# al.net
KiCad netlist of a schematic drawn in EAGLE
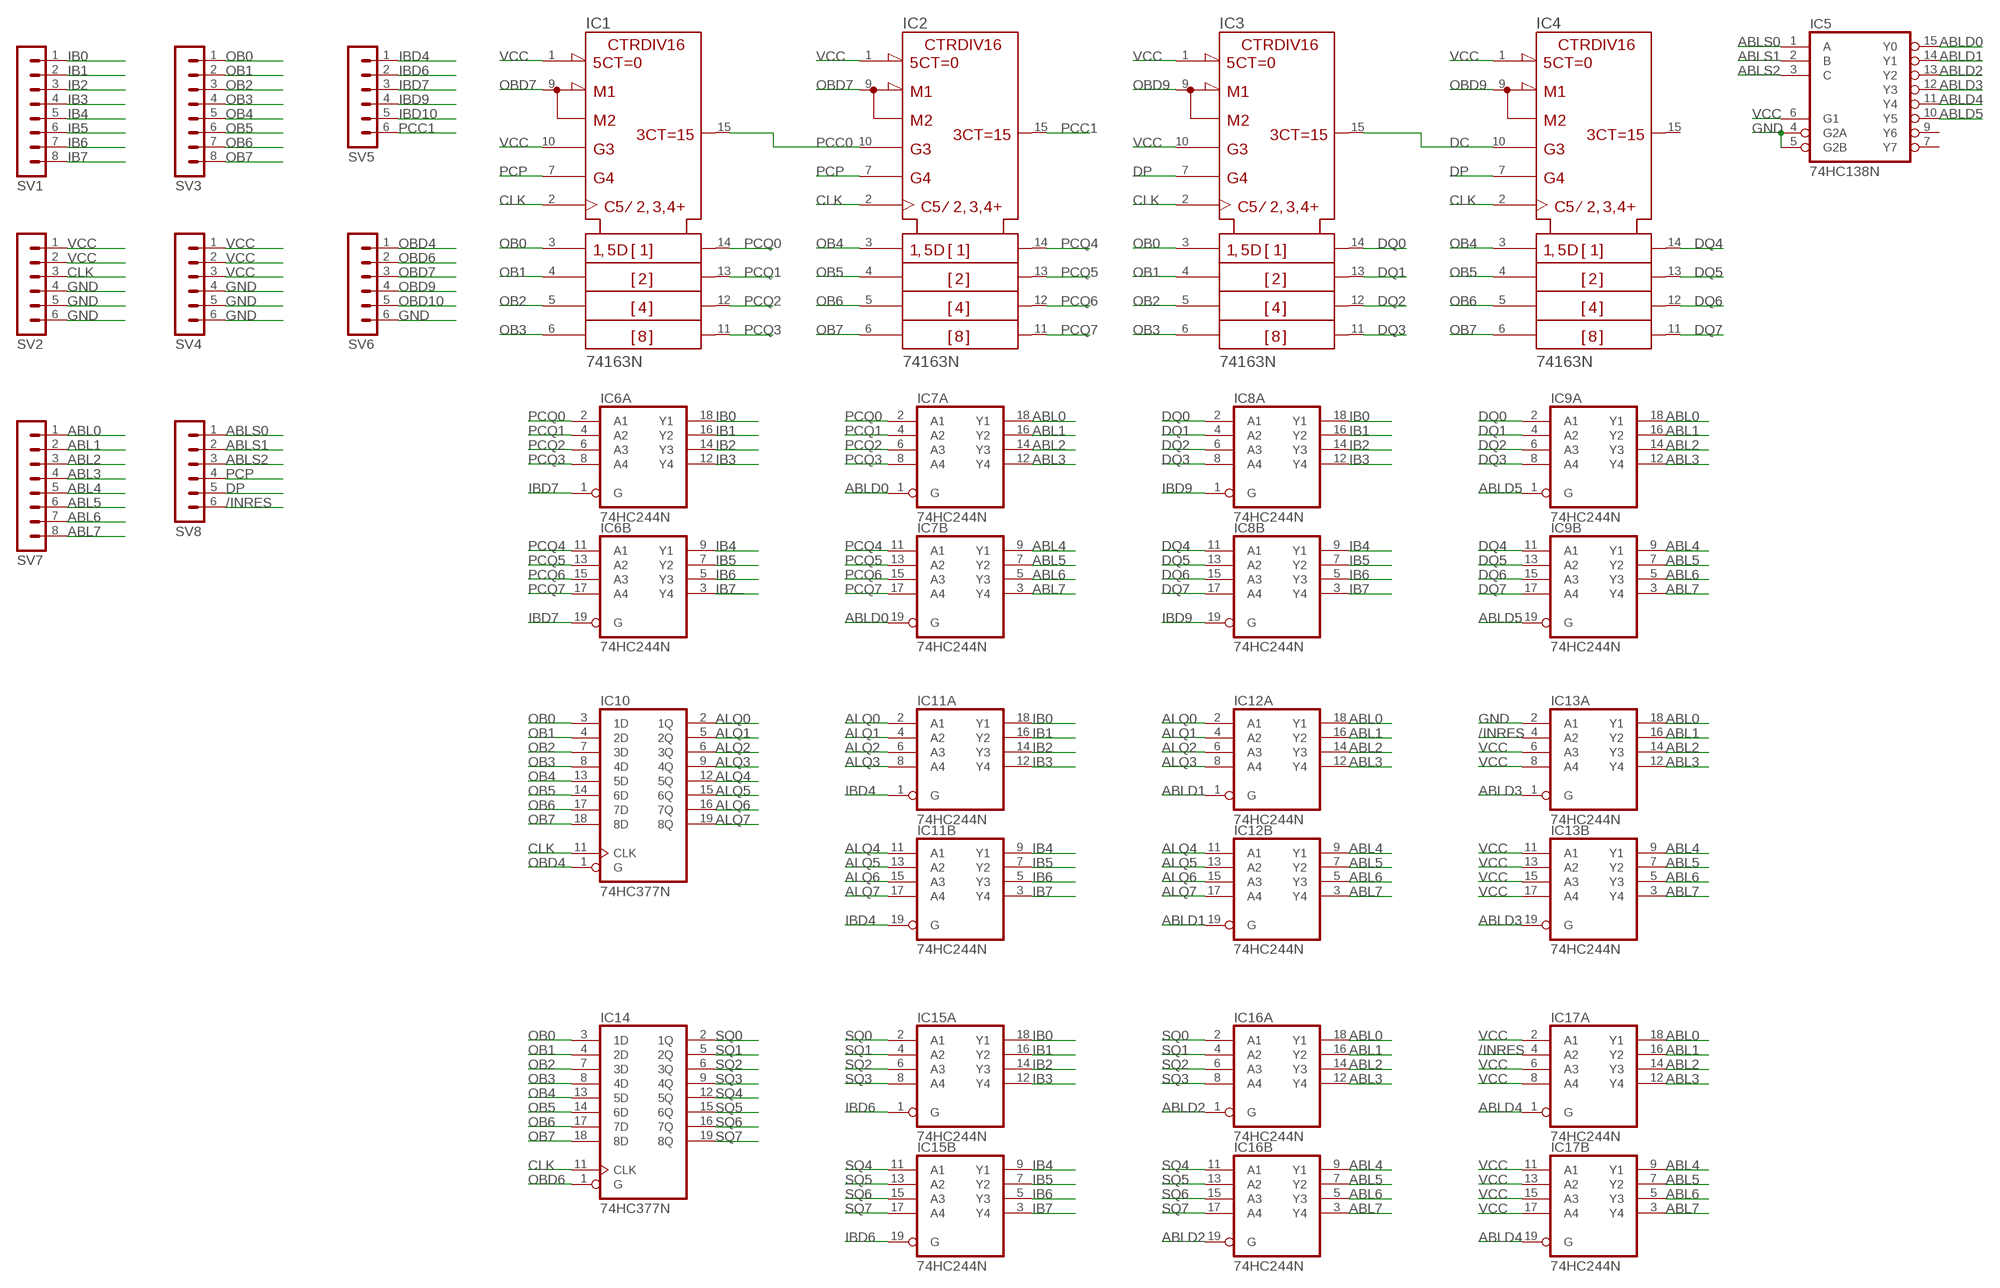
[diagram p0: schematic, sheet 1]

(export (version "E")
  (design (tool "Eeschema 10.0.6"))
  (components
    (comp (ref "IC1")
      (value "74163N")
      (footprint "eagle-import:DIL16")
      (libsource (lib "eagle-import") (part "74163N"))
    )
    (comp (ref "IC2")
      (value "74163N")
      (footprint "eagle-import:DIL16")
      (libsource (lib "eagle-import") (part "74163N"))
    )
    (comp (ref "IC3")
      (value "74163N")
      (footprint "eagle-import:DIL16")
      (libsource (lib "eagle-import") (part "74163N"))
    )
    (comp (ref "IC4")
      (value "74163N")
      (footprint "eagle-import:DIL16")
      (libsource (lib "eagle-import") (part "74163N"))
    )
    (comp (ref "IC5")
      (value "74HC138N")
      (footprint "eagle-import:DIL16")
      (libsource (lib "eagle-import") (part "74138NHC"))
    )
    (comp (ref "IC6")
      (value "74HC244N")
      (footprint "eagle-import:DIL20")
      (libsource (lib "eagle-import") (part "74244NHC"))
    )
    (comp (ref "IC7")
      (value "74HC244N")
      (footprint "eagle-import:DIL20")
      (libsource (lib "eagle-import") (part "74244NHC"))
    )
    (comp (ref "IC8")
      (value "74HC244N")
      (footprint "eagle-import:DIL20")
      (libsource (lib "eagle-import") (part "74244NHC"))
    )
    (comp (ref "IC9")
      (value "74HC244N")
      (footprint "eagle-import:DIL20")
      (libsource (lib "eagle-import") (part "74244NHC"))
    )
    (comp (ref "IC10")
      (value "74HC377N")
      (footprint "eagle-import:DIL20")
      (libsource (lib "eagle-import") (part "74377NHC"))
    )
    (comp (ref "IC11")
      (value "74HC244N")
      (footprint "eagle-import:DIL20")
      (libsource (lib "eagle-import") (part "74244NHC"))
    )
    (comp (ref "IC12")
      (value "74HC244N")
      (footprint "eagle-import:DIL20")
      (libsource (lib "eagle-import") (part "74244NHC"))
    )
    (comp (ref "IC13")
      (value "74HC244N")
      (footprint "eagle-import:DIL20")
      (libsource (lib "eagle-import") (part "74244NHC"))
    )
    (comp (ref "IC14")
      (value "74HC377N")
      (footprint "eagle-import:DIL20")
      (libsource (lib "eagle-import") (part "74377NHC"))
    )
    (comp (ref "IC15")
      (value "74HC244N")
      (footprint "eagle-import:DIL20")
      (libsource (lib "eagle-import") (part "74244NHC"))
    )
    (comp (ref "IC16")
      (value "74HC244N")
      (footprint "eagle-import:DIL20")
      (libsource (lib "eagle-import") (part "74244NHC"))
    )
    (comp (ref "IC17")
      (value "74HC244N")
      (footprint "eagle-import:DIL20")
      (libsource (lib "eagle-import") (part "74244NHC"))
    )
    (comp (ref "SV1")
      (value "MA08-1")
      (footprint "eagle-import:MA08-1")
      (libsource (lib "eagle-import") (part "MA08-1"))
    )
    (comp (ref "SV2")
      (value "MA06-1")
      (footprint "eagle-import:MA06-1")
      (libsource (lib "eagle-import") (part "MA06-1"))
    )
    (comp (ref "SV3")
      (value "MA08-1")
      (footprint "eagle-import:MA08-1")
      (libsource (lib "eagle-import") (part "MA08-1"))
    )
    (comp (ref "SV4")
      (value "MA06-1")
      (footprint "eagle-import:MA06-1")
      (libsource (lib "eagle-import") (part "MA06-1"))
    )
    (comp (ref "SV5")
      (value "MA06-1")
      (footprint "eagle-import:MA06-1")
      (libsource (lib "eagle-import") (part "MA06-1"))
    )
    (comp (ref "SV6")
      (value "MA06-1")
      (footprint "eagle-import:MA06-1")
      (libsource (lib "eagle-import") (part "MA06-1"))
    )
    (comp (ref "SV7")
      (value "MA08-1")
      (footprint "eagle-import:MA08-1")
      (libsource (lib "eagle-import") (part "MA08-1"))
    )
    (comp (ref "SV8")
      (value "MA06-1")
      (footprint "eagle-import:MA06-1")
      (libsource (lib "eagle-import") (part "MA06-1"))
    )
  )
  (nets
    (net (code "1") (name "/ABL0") (class "Default")
      (node (ref "IC12") (pin "18") (pinfunction "Y1_18") (pintype "tri_state"))
      (node (ref "IC13") (pin "18") (pinfunction "Y1_18") (pintype "tri_state"))
      (node (ref "IC16") (pin "18") (pinfunction "Y1_18") (pintype "tri_state"))
      (node (ref "IC17") (pin "18") (pinfunction "Y1_18") (pintype "tri_state"))
      (node (ref "IC7") (pin "18") (pinfunction "Y1_18") (pintype "tri_state"))
      (node (ref "IC9") (pin "18") (pinfunction "Y1_18") (pintype "tri_state"))
      (node (ref "SV7") (pin "1") (pinfunction "1_1") (pintype "passive"))
    )
    (net (code "2") (name "/ABL1") (class "Default")
      (node (ref "IC12") (pin "16") (pinfunction "Y2_16") (pintype "tri_state"))
      (node (ref "IC13") (pin "16") (pinfunction "Y2_16") (pintype "tri_state"))
      (node (ref "IC16") (pin "16") (pinfunction "Y2_16") (pintype "tri_state"))
      (node (ref "IC17") (pin "16") (pinfunction "Y2_16") (pintype "tri_state"))
      (node (ref "IC7") (pin "16") (pinfunction "Y2_16") (pintype "tri_state"))
      (node (ref "IC9") (pin "16") (pinfunction "Y2_16") (pintype "tri_state"))
      (node (ref "SV7") (pin "2") (pinfunction "2_2") (pintype "passive"))
    )
    (net (code "3") (name "/ABL2") (class "Default")
      (node (ref "IC12") (pin "14") (pinfunction "Y3_14") (pintype "tri_state"))
      (node (ref "IC13") (pin "14") (pinfunction "Y3_14") (pintype "tri_state"))
      (node (ref "IC16") (pin "14") (pinfunction "Y3_14") (pintype "tri_state"))
      (node (ref "IC17") (pin "14") (pinfunction "Y3_14") (pintype "tri_state"))
      (node (ref "IC7") (pin "14") (pinfunction "Y3_14") (pintype "tri_state"))
      (node (ref "IC9") (pin "14") (pinfunction "Y3_14") (pintype "tri_state"))
      (node (ref "SV7") (pin "3") (pinfunction "3_3") (pintype "passive"))
    )
    (net (code "4") (name "/ABL3") (class "Default")
      (node (ref "IC12") (pin "12") (pinfunction "Y4_12") (pintype "tri_state"))
      (node (ref "IC13") (pin "12") (pinfunction "Y4_12") (pintype "tri_state"))
      (node (ref "IC16") (pin "12") (pinfunction "Y4_12") (pintype "tri_state"))
      (node (ref "IC17") (pin "12") (pinfunction "Y4_12") (pintype "tri_state"))
      (node (ref "IC7") (pin "12") (pinfunction "Y4_12") (pintype "tri_state"))
      (node (ref "IC9") (pin "12") (pinfunction "Y4_12") (pintype "tri_state"))
      (node (ref "SV7") (pin "4") (pinfunction "4_4") (pintype "passive"))
    )
    (net (code "5") (name "/ABL4") (class "Default")
      (node (ref "IC12") (pin "9") (pinfunction "Y1_9") (pintype "tri_state"))
      (node (ref "IC13") (pin "9") (pinfunction "Y1_9") (pintype "tri_state"))
      (node (ref "IC16") (pin "9") (pinfunction "Y1_9") (pintype "tri_state"))
      (node (ref "IC17") (pin "9") (pinfunction "Y1_9") (pintype "tri_state"))
      (node (ref "IC7") (pin "9") (pinfunction "Y1_9") (pintype "tri_state"))
      (node (ref "IC9") (pin "9") (pinfunction "Y1_9") (pintype "tri_state"))
      (node (ref "SV7") (pin "5") (pinfunction "5_5") (pintype "passive"))
    )
    (net (code "6") (name "/ABL5") (class "Default")
      (node (ref "IC12") (pin "7") (pinfunction "Y2_7") (pintype "tri_state"))
      (node (ref "IC13") (pin "7") (pinfunction "Y2_7") (pintype "tri_state"))
      (node (ref "IC16") (pin "7") (pinfunction "Y2_7") (pintype "tri_state"))
      (node (ref "IC17") (pin "7") (pinfunction "Y2_7") (pintype "tri_state"))
      (node (ref "IC7") (pin "7") (pinfunction "Y2_7") (pintype "tri_state"))
      (node (ref "IC9") (pin "7") (pinfunction "Y2_7") (pintype "tri_state"))
      (node (ref "SV7") (pin "6") (pinfunction "6_6") (pintype "passive"))
    )
    (net (code "7") (name "/ABL6") (class "Default")
      (node (ref "IC12") (pin "5") (pinfunction "Y3_5") (pintype "tri_state"))
      (node (ref "IC13") (pin "5") (pinfunction "Y3_5") (pintype "tri_state"))
      (node (ref "IC16") (pin "5") (pinfunction "Y3_5") (pintype "tri_state"))
      (node (ref "IC17") (pin "5") (pinfunction "Y3_5") (pintype "tri_state"))
      (node (ref "IC7") (pin "5") (pinfunction "Y3_5") (pintype "tri_state"))
      (node (ref "IC9") (pin "5") (pinfunction "Y3_5") (pintype "tri_state"))
      (node (ref "SV7") (pin "7") (pinfunction "7_7") (pintype "passive"))
    )
    (net (code "8") (name "/ABL7") (class "Default")
      (node (ref "IC12") (pin "3") (pinfunction "Y4_3") (pintype "tri_state"))
      (node (ref "IC13") (pin "3") (pinfunction "Y4_3") (pintype "tri_state"))
      (node (ref "IC16") (pin "3") (pinfunction "Y4_3") (pintype "tri_state"))
      (node (ref "IC17") (pin "3") (pinfunction "Y4_3") (pintype "tri_state"))
      (node (ref "IC7") (pin "3") (pinfunction "Y4_3") (pintype "tri_state"))
      (node (ref "IC9") (pin "3") (pinfunction "Y4_3") (pintype "tri_state"))
      (node (ref "SV7") (pin "8") (pinfunction "8_8") (pintype "passive"))
    )
    (net (code "9") (name "/ABLD0") (class "Default")
      (node (ref "IC5") (pin "15") (pinfunction "Y0_15") (pintype "output"))
      (node (ref "IC7") (pin "1") (pinfunction "G_1") (pintype "input"))
      (node (ref "IC7") (pin "19") (pinfunction "G_19") (pintype "input"))
    )
    (net (code "10") (name "/ABLD1") (class "Default")
      (node (ref "IC12") (pin "1") (pinfunction "G_1") (pintype "input"))
      (node (ref "IC12") (pin "19") (pinfunction "G_19") (pintype "input"))
      (node (ref "IC5") (pin "14") (pinfunction "Y1_14") (pintype "output"))
    )
    (net (code "11") (name "/ABLD2") (class "Default")
      (node (ref "IC16") (pin "1") (pinfunction "G_1") (pintype "input"))
      (node (ref "IC16") (pin "19") (pinfunction "G_19") (pintype "input"))
      (node (ref "IC5") (pin "13") (pinfunction "Y2_13") (pintype "output"))
    )
    (net (code "12") (name "/ABLD3") (class "Default")
      (node (ref "IC13") (pin "1") (pinfunction "G_1") (pintype "input"))
      (node (ref "IC13") (pin "19") (pinfunction "G_19") (pintype "input"))
      (node (ref "IC5") (pin "12") (pinfunction "Y3_12") (pintype "output"))
    )
    (net (code "13") (name "/ABLD4") (class "Default")
      (node (ref "IC17") (pin "1") (pinfunction "G_1") (pintype "input"))
      (node (ref "IC17") (pin "19") (pinfunction "G_19") (pintype "input"))
      (node (ref "IC5") (pin "11") (pinfunction "Y4_11") (pintype "output"))
    )
    (net (code "14") (name "/ABLD5") (class "Default")
      (node (ref "IC5") (pin "10") (pinfunction "Y5_10") (pintype "output"))
      (node (ref "IC9") (pin "1") (pinfunction "G_1") (pintype "input"))
      (node (ref "IC9") (pin "19") (pinfunction "G_19") (pintype "input"))
    )
    (net (code "15") (name "/ABLS0") (class "Default")
      (node (ref "IC5") (pin "1") (pinfunction "A_1") (pintype "input"))
      (node (ref "SV8") (pin "1") (pinfunction "1_1") (pintype "passive"))
    )
    (net (code "16") (name "/ABLS1") (class "Default")
      (node (ref "IC5") (pin "2") (pinfunction "B_2") (pintype "input"))
      (node (ref "SV8") (pin "2") (pinfunction "2_2") (pintype "passive"))
    )
    (net (code "17") (name "/ABLS2") (class "Default")
      (node (ref "IC5") (pin "3") (pinfunction "C_3") (pintype "input"))
      (node (ref "SV8") (pin "3") (pinfunction "3_3") (pintype "passive"))
    )
    (net (code "18") (name "/ALQ0") (class "Default")
      (node (ref "IC10") (pin "2") (pinfunction "1Q_2") (pintype "output"))
      (node (ref "IC11") (pin "2") (pinfunction "A1_2") (pintype "input"))
      (node (ref "IC12") (pin "2") (pinfunction "A1_2") (pintype "input"))
    )
    (net (code "19") (name "/ALQ1") (class "Default")
      (node (ref "IC10") (pin "5") (pinfunction "2Q_5") (pintype "output"))
      (node (ref "IC11") (pin "4") (pinfunction "A2_4") (pintype "input"))
      (node (ref "IC12") (pin "4") (pinfunction "A2_4") (pintype "input"))
    )
    (net (code "20") (name "/ALQ2") (class "Default")
      (node (ref "IC10") (pin "6") (pinfunction "3Q_6") (pintype "output"))
      (node (ref "IC11") (pin "6") (pinfunction "A3_6") (pintype "input"))
      (node (ref "IC12") (pin "6") (pinfunction "A3_6") (pintype "input"))
    )
    (net (code "21") (name "/ALQ3") (class "Default")
      (node (ref "IC10") (pin "9") (pinfunction "4Q_9") (pintype "output"))
      (node (ref "IC11") (pin "8") (pinfunction "A4_8") (pintype "input"))
      (node (ref "IC12") (pin "8") (pinfunction "A4_8") (pintype "input"))
    )
    (net (code "22") (name "/ALQ4") (class "Default")
      (node (ref "IC10") (pin "12") (pinfunction "5Q_12") (pintype "output"))
      (node (ref "IC11") (pin "11") (pinfunction "A1_11") (pintype "input"))
      (node (ref "IC12") (pin "11") (pinfunction "A1_11") (pintype "input"))
    )
    (net (code "23") (name "/ALQ5") (class "Default")
      (node (ref "IC10") (pin "15") (pinfunction "6Q_15") (pintype "output"))
      (node (ref "IC11") (pin "13") (pinfunction "A2_13") (pintype "input"))
      (node (ref "IC12") (pin "13") (pinfunction "A2_13") (pintype "input"))
    )
    (net (code "24") (name "/ALQ6") (class "Default")
      (node (ref "IC10") (pin "16") (pinfunction "7Q_16") (pintype "output"))
      (node (ref "IC11") (pin "15") (pinfunction "A3_15") (pintype "input"))
      (node (ref "IC12") (pin "15") (pinfunction "A3_15") (pintype "input"))
    )
    (net (code "25") (name "/ALQ7") (class "Default")
      (node (ref "IC10") (pin "19") (pinfunction "8Q_19") (pintype "output"))
      (node (ref "IC11") (pin "17") (pinfunction "A4_17") (pintype "input"))
      (node (ref "IC12") (pin "17") (pinfunction "A4_17") (pintype "input"))
    )
    (net (code "26") (name "/CLK") (class "Default")
      (node (ref "IC1") (pin "2") (pinfunction "CLK_2") (pintype "input"))
      (node (ref "IC10") (pin "11") (pinfunction "CLK_11") (pintype "input"))
      (node (ref "IC14") (pin "11") (pinfunction "CLK_11") (pintype "input"))
      (node (ref "IC2") (pin "2") (pinfunction "CLK_2") (pintype "input"))
      (node (ref "IC3") (pin "2") (pinfunction "CLK_2") (pintype "input"))
      (node (ref "IC4") (pin "2") (pinfunction "CLK_2") (pintype "input"))
      (node (ref "SV2") (pin "3") (pinfunction "3_3") (pintype "passive"))
    )
    (net (code "27") (name "/DC") (class "Default")
      (node (ref "IC3") (pin "15") (pinfunction "RCO_15") (pintype "output"))
      (node (ref "IC4") (pin "10") (pinfunction "ENT_10") (pintype "input"))
    )
    (net (code "28") (name "/DP") (class "Default")
      (node (ref "IC3") (pin "7") (pinfunction "ENP_7") (pintype "input"))
      (node (ref "IC4") (pin "7") (pinfunction "ENP_7") (pintype "input"))
      (node (ref "SV8") (pin "5") (pinfunction "5_5") (pintype "passive"))
    )
    (net (code "29") (name "/DQ0") (class "Default")
      (node (ref "IC3") (pin "14") (pinfunction "QA_14") (pintype "output"))
      (node (ref "IC8") (pin "2") (pinfunction "A1_2") (pintype "input"))
      (node (ref "IC9") (pin "2") (pinfunction "A1_2") (pintype "input"))
    )
    (net (code "30") (name "/DQ1") (class "Default")
      (node (ref "IC3") (pin "13") (pinfunction "QB_13") (pintype "output"))
      (node (ref "IC8") (pin "4") (pinfunction "A2_4") (pintype "input"))
      (node (ref "IC9") (pin "4") (pinfunction "A2_4") (pintype "input"))
    )
    (net (code "31") (name "/DQ2") (class "Default")
      (node (ref "IC3") (pin "12") (pinfunction "QC_12") (pintype "output"))
      (node (ref "IC8") (pin "6") (pinfunction "A3_6") (pintype "input"))
      (node (ref "IC9") (pin "6") (pinfunction "A3_6") (pintype "input"))
    )
    (net (code "32") (name "/DQ3") (class "Default")
      (node (ref "IC3") (pin "11") (pinfunction "QD_11") (pintype "output"))
      (node (ref "IC8") (pin "8") (pinfunction "A4_8") (pintype "input"))
      (node (ref "IC9") (pin "8") (pinfunction "A4_8") (pintype "input"))
    )
    (net (code "33") (name "/DQ4") (class "Default")
      (node (ref "IC4") (pin "14") (pinfunction "QA_14") (pintype "output"))
      (node (ref "IC8") (pin "11") (pinfunction "A1_11") (pintype "input"))
      (node (ref "IC9") (pin "11") (pinfunction "A1_11") (pintype "input"))
    )
    (net (code "34") (name "/DQ5") (class "Default")
      (node (ref "IC4") (pin "13") (pinfunction "QB_13") (pintype "output"))
      (node (ref "IC8") (pin "13") (pinfunction "A2_13") (pintype "input"))
      (node (ref "IC9") (pin "13") (pinfunction "A2_13") (pintype "input"))
    )
    (net (code "35") (name "/DQ6") (class "Default")
      (node (ref "IC4") (pin "12") (pinfunction "QC_12") (pintype "output"))
      (node (ref "IC8") (pin "15") (pinfunction "A3_15") (pintype "input"))
      (node (ref "IC9") (pin "15") (pinfunction "A3_15") (pintype "input"))
    )
    (net (code "36") (name "/DQ7") (class "Default")
      (node (ref "IC4") (pin "11") (pinfunction "QD_11") (pintype "output"))
      (node (ref "IC8") (pin "17") (pinfunction "A4_17") (pintype "input"))
      (node (ref "IC9") (pin "17") (pinfunction "A4_17") (pintype "input"))
    )
    (net (code "37") (name "/GND") (class "Default")
      (node (ref "IC13") (pin "2") (pinfunction "A1_2") (pintype "input"))
      (node (ref "IC5") (pin "4") (pinfunction "G2A_4") (pintype "input"))
      (node (ref "IC5") (pin "5") (pinfunction "G2B_5") (pintype "input"))
      (node (ref "SV2") (pin "4") (pinfunction "4_4") (pintype "passive"))
      (node (ref "SV2") (pin "5") (pinfunction "5_5") (pintype "passive"))
      (node (ref "SV2") (pin "6") (pinfunction "6_6") (pintype "passive"))
      (node (ref "SV4") (pin "4") (pinfunction "4_4") (pintype "passive"))
      (node (ref "SV4") (pin "5") (pinfunction "5_5") (pintype "passive"))
      (node (ref "SV4") (pin "6") (pinfunction "6_6") (pintype "passive"))
      (node (ref "SV6") (pin "6") (pinfunction "6_6") (pintype "passive"))
    )
    (net (code "38") (name "/IB0") (class "Default")
      (node (ref "IC11") (pin "18") (pinfunction "Y1_18") (pintype "tri_state"))
      (node (ref "IC15") (pin "18") (pinfunction "Y1_18") (pintype "tri_state"))
      (node (ref "IC6") (pin "18") (pinfunction "Y1_18") (pintype "tri_state"))
      (node (ref "IC8") (pin "18") (pinfunction "Y1_18") (pintype "tri_state"))
      (node (ref "SV1") (pin "1") (pinfunction "1_1") (pintype "passive"))
    )
    (net (code "39") (name "/IB1") (class "Default")
      (node (ref "IC11") (pin "16") (pinfunction "Y2_16") (pintype "tri_state"))
      (node (ref "IC15") (pin "16") (pinfunction "Y2_16") (pintype "tri_state"))
      (node (ref "IC6") (pin "16") (pinfunction "Y2_16") (pintype "tri_state"))
      (node (ref "IC8") (pin "16") (pinfunction "Y2_16") (pintype "tri_state"))
      (node (ref "SV1") (pin "2") (pinfunction "2_2") (pintype "passive"))
    )
    (net (code "40") (name "/IB2") (class "Default")
      (node (ref "IC11") (pin "14") (pinfunction "Y3_14") (pintype "tri_state"))
      (node (ref "IC15") (pin "14") (pinfunction "Y3_14") (pintype "tri_state"))
      (node (ref "IC6") (pin "14") (pinfunction "Y3_14") (pintype "tri_state"))
      (node (ref "IC8") (pin "14") (pinfunction "Y3_14") (pintype "tri_state"))
      (node (ref "SV1") (pin "3") (pinfunction "3_3") (pintype "passive"))
    )
    (net (code "41") (name "/IB3") (class "Default")
      (node (ref "IC11") (pin "12") (pinfunction "Y4_12") (pintype "tri_state"))
      (node (ref "IC15") (pin "12") (pinfunction "Y4_12") (pintype "tri_state"))
      (node (ref "IC6") (pin "12") (pinfunction "Y4_12") (pintype "tri_state"))
      (node (ref "IC8") (pin "12") (pinfunction "Y4_12") (pintype "tri_state"))
      (node (ref "SV1") (pin "4") (pinfunction "4_4") (pintype "passive"))
    )
    (net (code "42") (name "/IB4") (class "Default")
      (node (ref "IC11") (pin "9") (pinfunction "Y1_9") (pintype "tri_state"))
      (node (ref "IC15") (pin "9") (pinfunction "Y1_9") (pintype "tri_state"))
      (node (ref "IC6") (pin "9") (pinfunction "Y1_9") (pintype "tri_state"))
      (node (ref "IC8") (pin "9") (pinfunction "Y1_9") (pintype "tri_state"))
      (node (ref "SV1") (pin "5") (pinfunction "5_5") (pintype "passive"))
    )
    (net (code "43") (name "/IB5") (class "Default")
      (node (ref "IC11") (pin "7") (pinfunction "Y2_7") (pintype "tri_state"))
      (node (ref "IC15") (pin "7") (pinfunction "Y2_7") (pintype "tri_state"))
      (node (ref "IC6") (pin "7") (pinfunction "Y2_7") (pintype "tri_state"))
      (node (ref "IC8") (pin "7") (pinfunction "Y2_7") (pintype "tri_state"))
      (node (ref "SV1") (pin "6") (pinfunction "6_6") (pintype "passive"))
    )
    (net (code "44") (name "/IB6") (class "Default")
      (node (ref "IC11") (pin "5") (pinfunction "Y3_5") (pintype "tri_state"))
      (node (ref "IC15") (pin "5") (pinfunction "Y3_5") (pintype "tri_state"))
      (node (ref "IC6") (pin "5") (pinfunction "Y3_5") (pintype "tri_state"))
      (node (ref "IC8") (pin "5") (pinfunction "Y3_5") (pintype "tri_state"))
      (node (ref "SV1") (pin "7") (pinfunction "7_7") (pintype "passive"))
    )
    (net (code "45") (name "/IB7") (class "Default")
      (node (ref "IC11") (pin "3") (pinfunction "Y4_3") (pintype "tri_state"))
      (node (ref "IC15") (pin "3") (pinfunction "Y4_3") (pintype "tri_state"))
      (node (ref "IC6") (pin "3") (pinfunction "Y4_3") (pintype "tri_state"))
      (node (ref "IC8") (pin "3") (pinfunction "Y4_3") (pintype "tri_state"))
      (node (ref "SV1") (pin "8") (pinfunction "8_8") (pintype "passive"))
    )
    (net (code "46") (name "/IBD4") (class "Default")
      (node (ref "IC11") (pin "1") (pinfunction "G_1") (pintype "input"))
      (node (ref "IC11") (pin "19") (pinfunction "G_19") (pintype "input"))
      (node (ref "SV5") (pin "1") (pinfunction "1_1") (pintype "passive"))
    )
    (net (code "47") (name "/IBD6") (class "Default")
      (node (ref "IC15") (pin "1") (pinfunction "G_1") (pintype "input"))
      (node (ref "IC15") (pin "19") (pinfunction "G_19") (pintype "input"))
      (node (ref "SV5") (pin "2") (pinfunction "2_2") (pintype "passive"))
    )
    (net (code "48") (name "/IBD7") (class "Default")
      (node (ref "IC6") (pin "1") (pinfunction "G_1") (pintype "input"))
      (node (ref "IC6") (pin "19") (pinfunction "G_19") (pintype "input"))
      (node (ref "SV5") (pin "3") (pinfunction "3_3") (pintype "passive"))
    )
    (net (code "49") (name "/IBD9") (class "Default")
      (node (ref "IC8") (pin "1") (pinfunction "G_1") (pintype "input"))
      (node (ref "IC8") (pin "19") (pinfunction "G_19") (pintype "input"))
      (node (ref "SV5") (pin "4") (pinfunction "4_4") (pintype "passive"))
    )
    (net (code "50") (name "/IBD10") (class "Default")
      (node (ref "SV5") (pin "5") (pinfunction "5_5") (pintype "passive"))
    )
    (net (code "51") (name "/OB0") (class "Default")
      (node (ref "IC1") (pin "3") (pinfunction "A_3") (pintype "input"))
      (node (ref "IC10") (pin "3") (pinfunction "1D_3") (pintype "input"))
      (node (ref "IC14") (pin "3") (pinfunction "1D_3") (pintype "input"))
      (node (ref "IC3") (pin "3") (pinfunction "A_3") (pintype "input"))
      (node (ref "SV3") (pin "1") (pinfunction "1_1") (pintype "passive"))
    )
    (net (code "52") (name "/OB1") (class "Default")
      (node (ref "IC1") (pin "4") (pinfunction "B_4") (pintype "input"))
      (node (ref "IC10") (pin "4") (pinfunction "2D_4") (pintype "input"))
      (node (ref "IC14") (pin "4") (pinfunction "2D_4") (pintype "input"))
      (node (ref "IC3") (pin "4") (pinfunction "B_4") (pintype "input"))
      (node (ref "SV3") (pin "2") (pinfunction "2_2") (pintype "passive"))
    )
    (net (code "53") (name "/OB2") (class "Default")
      (node (ref "IC1") (pin "5") (pinfunction "C_5") (pintype "input"))
      (node (ref "IC10") (pin "7") (pinfunction "3D_7") (pintype "input"))
      (node (ref "IC14") (pin "7") (pinfunction "3D_7") (pintype "input"))
      (node (ref "IC3") (pin "5") (pinfunction "C_5") (pintype "input"))
      (node (ref "SV3") (pin "3") (pinfunction "3_3") (pintype "passive"))
    )
    (net (code "54") (name "/OB3") (class "Default")
      (node (ref "IC1") (pin "6") (pinfunction "D_6") (pintype "input"))
      (node (ref "IC10") (pin "8") (pinfunction "4D_8") (pintype "input"))
      (node (ref "IC14") (pin "8") (pinfunction "4D_8") (pintype "input"))
      (node (ref "IC3") (pin "6") (pinfunction "D_6") (pintype "input"))
      (node (ref "SV3") (pin "4") (pinfunction "4_4") (pintype "passive"))
    )
    (net (code "55") (name "/OB4") (class "Default")
      (node (ref "IC10") (pin "13") (pinfunction "5D_13") (pintype "input"))
      (node (ref "IC14") (pin "13") (pinfunction "5D_13") (pintype "input"))
      (node (ref "IC2") (pin "3") (pinfunction "A_3") (pintype "input"))
      (node (ref "IC4") (pin "3") (pinfunction "A_3") (pintype "input"))
      (node (ref "SV3") (pin "5") (pinfunction "5_5") (pintype "passive"))
    )
    (net (code "56") (name "/OB5") (class "Default")
      (node (ref "IC10") (pin "14") (pinfunction "6D_14") (pintype "input"))
      (node (ref "IC14") (pin "14") (pinfunction "6D_14") (pintype "input"))
      (node (ref "IC2") (pin "4") (pinfunction "B_4") (pintype "input"))
      (node (ref "IC4") (pin "4") (pinfunction "B_4") (pintype "input"))
      (node (ref "SV3") (pin "6") (pinfunction "6_6") (pintype "passive"))
    )
    (net (code "57") (name "/OB6") (class "Default")
      (node (ref "IC10") (pin "17") (pinfunction "7D_17") (pintype "input"))
      (node (ref "IC14") (pin "17") (pinfunction "7D_17") (pintype "input"))
      (node (ref "IC2") (pin "5") (pinfunction "C_5") (pintype "input"))
      (node (ref "IC4") (pin "5") (pinfunction "C_5") (pintype "input"))
      (node (ref "SV3") (pin "7") (pinfunction "7_7") (pintype "passive"))
    )
    (net (code "58") (name "/OB7") (class "Default")
      (node (ref "IC10") (pin "18") (pinfunction "8D_18") (pintype "input"))
      (node (ref "IC14") (pin "18") (pinfunction "8D_18") (pintype "input"))
      (node (ref "IC2") (pin "6") (pinfunction "D_6") (pintype "input"))
      (node (ref "IC4") (pin "6") (pinfunction "D_6") (pintype "input"))
      (node (ref "SV3") (pin "8") (pinfunction "8_8") (pintype "passive"))
    )
    (net (code "59") (name "/OBD4") (class "Default")
      (node (ref "IC10") (pin "1") (pinfunction "G_1") (pintype "input"))
      (node (ref "SV6") (pin "1") (pinfunction "1_1") (pintype "passive"))
    )
    (net (code "60") (name "/OBD6") (class "Default")
      (node (ref "IC14") (pin "1") (pinfunction "G_1") (pintype "input"))
      (node (ref "SV6") (pin "2") (pinfunction "2_2") (pintype "passive"))
    )
    (net (code "61") (name "/OBD7") (class "Default")
      (node (ref "IC1") (pin "9") (pinfunction "~{LOAD}_9") (pintype "input"))
      (node (ref "IC2") (pin "9") (pinfunction "~{LOAD}_9") (pintype "input"))
      (node (ref "SV6") (pin "3") (pinfunction "3_3") (pintype "passive"))
    )
    (net (code "62") (name "/OBD9") (class "Default")
      (node (ref "IC3") (pin "9") (pinfunction "~{LOAD}_9") (pintype "input"))
      (node (ref "IC4") (pin "9") (pinfunction "~{LOAD}_9") (pintype "input"))
      (node (ref "SV6") (pin "4") (pinfunction "4_4") (pintype "passive"))
    )
    (net (code "63") (name "/OBD10") (class "Default")
      (node (ref "SV6") (pin "5") (pinfunction "5_5") (pintype "passive"))
    )
    (net (code "64") (name "/PCC0") (class "Default")
      (node (ref "IC1") (pin "15") (pinfunction "RCO_15") (pintype "output"))
      (node (ref "IC2") (pin "10") (pinfunction "ENT_10") (pintype "input"))
    )
    (net (code "65") (name "/PCC1") (class "Default")
      (node (ref "IC2") (pin "15") (pinfunction "RCO_15") (pintype "output"))
      (node (ref "SV5") (pin "6") (pinfunction "6_6") (pintype "passive"))
    )
    (net (code "66") (name "/PCP") (class "Default")
      (node (ref "IC1") (pin "7") (pinfunction "ENP_7") (pintype "input"))
      (node (ref "IC2") (pin "7") (pinfunction "ENP_7") (pintype "input"))
      (node (ref "SV8") (pin "4") (pinfunction "4_4") (pintype "passive"))
    )
    (net (code "67") (name "/PCQ0") (class "Default")
      (node (ref "IC1") (pin "14") (pinfunction "QA_14") (pintype "output"))
      (node (ref "IC6") (pin "2") (pinfunction "A1_2") (pintype "input"))
      (node (ref "IC7") (pin "2") (pinfunction "A1_2") (pintype "input"))
    )
    (net (code "68") (name "/PCQ1") (class "Default")
      (node (ref "IC1") (pin "13") (pinfunction "QB_13") (pintype "output"))
      (node (ref "IC6") (pin "4") (pinfunction "A2_4") (pintype "input"))
      (node (ref "IC7") (pin "4") (pinfunction "A2_4") (pintype "input"))
    )
    (net (code "69") (name "/PCQ2") (class "Default")
      (node (ref "IC1") (pin "12") (pinfunction "QC_12") (pintype "output"))
      (node (ref "IC6") (pin "6") (pinfunction "A3_6") (pintype "input"))
      (node (ref "IC7") (pin "6") (pinfunction "A3_6") (pintype "input"))
    )
    (net (code "70") (name "/PCQ3") (class "Default")
      (node (ref "IC1") (pin "11") (pinfunction "QD_11") (pintype "output"))
      (node (ref "IC6") (pin "8") (pinfunction "A4_8") (pintype "input"))
      (node (ref "IC7") (pin "8") (pinfunction "A4_8") (pintype "input"))
    )
    (net (code "71") (name "/PCQ4") (class "Default")
      (node (ref "IC2") (pin "14") (pinfunction "QA_14") (pintype "output"))
      (node (ref "IC6") (pin "11") (pinfunction "A1_11") (pintype "input"))
      (node (ref "IC7") (pin "11") (pinfunction "A1_11") (pintype "input"))
    )
    (net (code "72") (name "/PCQ5") (class "Default")
      (node (ref "IC2") (pin "13") (pinfunction "QB_13") (pintype "output"))
      (node (ref "IC6") (pin "13") (pinfunction "A2_13") (pintype "input"))
      (node (ref "IC7") (pin "13") (pinfunction "A2_13") (pintype "input"))
    )
    (net (code "73") (name "/PCQ6") (class "Default")
      (node (ref "IC2") (pin "12") (pinfunction "QC_12") (pintype "output"))
      (node (ref "IC6") (pin "15") (pinfunction "A3_15") (pintype "input"))
      (node (ref "IC7") (pin "15") (pinfunction "A3_15") (pintype "input"))
    )
    (net (code "74") (name "/PCQ7") (class "Default")
      (node (ref "IC2") (pin "11") (pinfunction "QD_11") (pintype "output"))
      (node (ref "IC6") (pin "17") (pinfunction "A4_17") (pintype "input"))
      (node (ref "IC7") (pin "17") (pinfunction "A4_17") (pintype "input"))
    )
    (net (code "75") (name "/SQ0") (class "Default")
      (node (ref "IC14") (pin "2") (pinfunction "1Q_2") (pintype "output"))
      (node (ref "IC15") (pin "2") (pinfunction "A1_2") (pintype "input"))
      (node (ref "IC16") (pin "2") (pinfunction "A1_2") (pintype "input"))
    )
    (net (code "76") (name "/SQ1") (class "Default")
      (node (ref "IC14") (pin "5") (pinfunction "2Q_5") (pintype "output"))
      (node (ref "IC15") (pin "4") (pinfunction "A2_4") (pintype "input"))
      (node (ref "IC16") (pin "4") (pinfunction "A2_4") (pintype "input"))
    )
    (net (code "77") (name "/SQ2") (class "Default")
      (node (ref "IC14") (pin "6") (pinfunction "3Q_6") (pintype "output"))
      (node (ref "IC15") (pin "6") (pinfunction "A3_6") (pintype "input"))
      (node (ref "IC16") (pin "6") (pinfunction "A3_6") (pintype "input"))
    )
    (net (code "78") (name "/SQ3") (class "Default")
      (node (ref "IC14") (pin "9") (pinfunction "4Q_9") (pintype "output"))
      (node (ref "IC15") (pin "8") (pinfunction "A4_8") (pintype "input"))
      (node (ref "IC16") (pin "8") (pinfunction "A4_8") (pintype "input"))
    )
    (net (code "79") (name "/SQ4") (class "Default")
      (node (ref "IC14") (pin "12") (pinfunction "5Q_12") (pintype "output"))
      (node (ref "IC15") (pin "11") (pinfunction "A1_11") (pintype "input"))
      (node (ref "IC16") (pin "11") (pinfunction "A1_11") (pintype "input"))
    )
    (net (code "80") (name "/SQ5") (class "Default")
      (node (ref "IC14") (pin "15") (pinfunction "6Q_15") (pintype "output"))
      (node (ref "IC15") (pin "13") (pinfunction "A2_13") (pintype "input"))
      (node (ref "IC16") (pin "13") (pinfunction "A2_13") (pintype "input"))
    )
    (net (code "81") (name "/SQ6") (class "Default")
      (node (ref "IC14") (pin "16") (pinfunction "7Q_16") (pintype "output"))
      (node (ref "IC15") (pin "15") (pinfunction "A3_15") (pintype "input"))
      (node (ref "IC16") (pin "15") (pinfunction "A3_15") (pintype "input"))
    )
    (net (code "82") (name "/SQ7") (class "Default")
      (node (ref "IC14") (pin "19") (pinfunction "8Q_19") (pintype "output"))
      (node (ref "IC15") (pin "17") (pinfunction "A4_17") (pintype "input"))
      (node (ref "IC16") (pin "17") (pinfunction "A4_17") (pintype "input"))
    )
    (net (code "83") (name "/VCC") (class "Default")
      (node (ref "IC1") (pin "1") (pinfunction "~{CLR}_1") (pintype "input"))
      (node (ref "IC1") (pin "10") (pinfunction "ENT_10") (pintype "input"))
      (node (ref "IC13") (pin "11") (pinfunction "A1_11") (pintype "input"))
      (node (ref "IC13") (pin "13") (pinfunction "A2_13") (pintype "input"))
      (node (ref "IC13") (pin "15") (pinfunction "A3_15") (pintype "input"))
      (node (ref "IC13") (pin "17") (pinfunction "A4_17") (pintype "input"))
      (node (ref "IC13") (pin "6") (pinfunction "A3_6") (pintype "input"))
      (node (ref "IC13") (pin "8") (pinfunction "A4_8") (pintype "input"))
      (node (ref "IC17") (pin "11") (pinfunction "A1_11") (pintype "input"))
      (node (ref "IC17") (pin "13") (pinfunction "A2_13") (pintype "input"))
      (node (ref "IC17") (pin "15") (pinfunction "A3_15") (pintype "input"))
      (node (ref "IC17") (pin "17") (pinfunction "A4_17") (pintype "input"))
      (node (ref "IC17") (pin "2") (pinfunction "A1_2") (pintype "input"))
      (node (ref "IC17") (pin "6") (pinfunction "A3_6") (pintype "input"))
      (node (ref "IC17") (pin "8") (pinfunction "A4_8") (pintype "input"))
      (node (ref "IC2") (pin "1") (pinfunction "~{CLR}_1") (pintype "input"))
      (node (ref "IC3") (pin "1") (pinfunction "~{CLR}_1") (pintype "input"))
      (node (ref "IC3") (pin "10") (pinfunction "ENT_10") (pintype "input"))
      (node (ref "IC4") (pin "1") (pinfunction "~{CLR}_1") (pintype "input"))
      (node (ref "IC5") (pin "6") (pinfunction "G1_6") (pintype "input"))
      (node (ref "SV2") (pin "1") (pinfunction "1_1") (pintype "passive"))
      (node (ref "SV2") (pin "2") (pinfunction "2_2") (pintype "passive"))
      (node (ref "SV4") (pin "1") (pinfunction "1_1") (pintype "passive"))
      (node (ref "SV4") (pin "2") (pinfunction "2_2") (pintype "passive"))
      (node (ref "SV4") (pin "3") (pinfunction "3_3") (pintype "passive"))
    )
    (net (code "84") (name "/{slash}INRES") (class "Default")
      (node (ref "IC13") (pin "4") (pinfunction "A2_4") (pintype "input"))
      (node (ref "IC17") (pin "4") (pinfunction "A2_4") (pintype "input"))
      (node (ref "SV8") (pin "6") (pinfunction "6_6") (pintype "passive"))
    )
    (net (code "85") (name "unconnected-(IC4C-RCO-Pad15)") (class "Default")
      (node (ref "IC4") (pin "15") (pinfunction "RCO_15") (pintype "output"))
    )
    (net (code "86") (name "unconnected-(IC5A-Y6-Pad9)") (class "Default")
      (node (ref "IC5") (pin "9") (pinfunction "Y6_9") (pintype "output"))
    )
    (net (code "87") (name "unconnected-(IC5A-Y7-Pad7)") (class "Default")
      (node (ref "IC5") (pin "7") (pinfunction "Y7_7") (pintype "output"))
    )
  )
)
